# Flash.net
KiCad netlist of a schematic drawn in Altium Designer
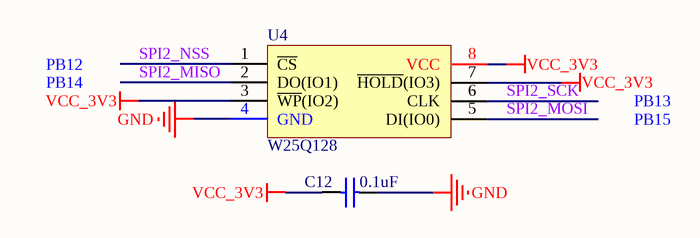
[diagram p0: Flash.SchDoc]

(export (version "E")
  (design (tool "Eeschema 10.0.6"))
  (components
    (comp (ref "C12")
      (value "0.1uF")
      (footprint "C0402_L")
      (description "贴片电容")
      (libsource (lib "0.1 - 电阻-电容-电感-晶振-晶体-磁珠-电位器") (part "C"))
    )
    (comp (ref "U4")
      (value "W25Q128")
      (footprint "WSON 6x5mm")
      (description "SPI Flash")
      (libsource (lib "USER_Lib") (part "W25Qxx"))
    )
  )
  (nets
    (net (code "1") (name "/SPI2_MISO") (class "Default")
      (node (ref "U4") (pin "2") (pinfunction "DO(IO1)_2") (pintype "passive"))
    )
    (net (code "2") (name "/SPI2_MOSI") (class "Default")
      (node (ref "U4") (pin "5") (pinfunction "DI(IO0)_5") (pintype "passive"))
    )
    (net (code "3") (name "/SPI2_NSS") (class "Default")
      (node (ref "U4") (pin "1") (pinfunction "~{CS}_1") (pintype "passive"))
    )
    (net (code "4") (name "/SPI2_SCK") (class "Default")
      (node (ref "U4") (pin "6") (pinfunction "CLK_6") (pintype "passive"))
    )
    (net (code "5") (name "GND") (class "Default")
      (node (ref "C12") (pin "1") (pinfunction "1_1") (pintype "passive"))
      (node (ref "U4") (pin "4") (pinfunction "GND_4") (pintype "passive"))
    )
    (net (code "6") (name "VCC_3V3") (class "Default")
      (node (ref "C12") (pin "2") (pinfunction "2_2") (pintype "passive"))
      (node (ref "U4") (pin "3") (pinfunction "~{WP}(IO2)_3") (pintype "passive"))
      (node (ref "U4") (pin "7") (pinfunction "~{HOLD}(IO3)_7") (pintype "passive"))
      (node (ref "U4") (pin "8") (pinfunction "VCC_8") (pintype "passive"))
    )
  )
)
